# RPi_Extension_atx_power.net
KiCad netlist of a schematic drawn in EAGLE
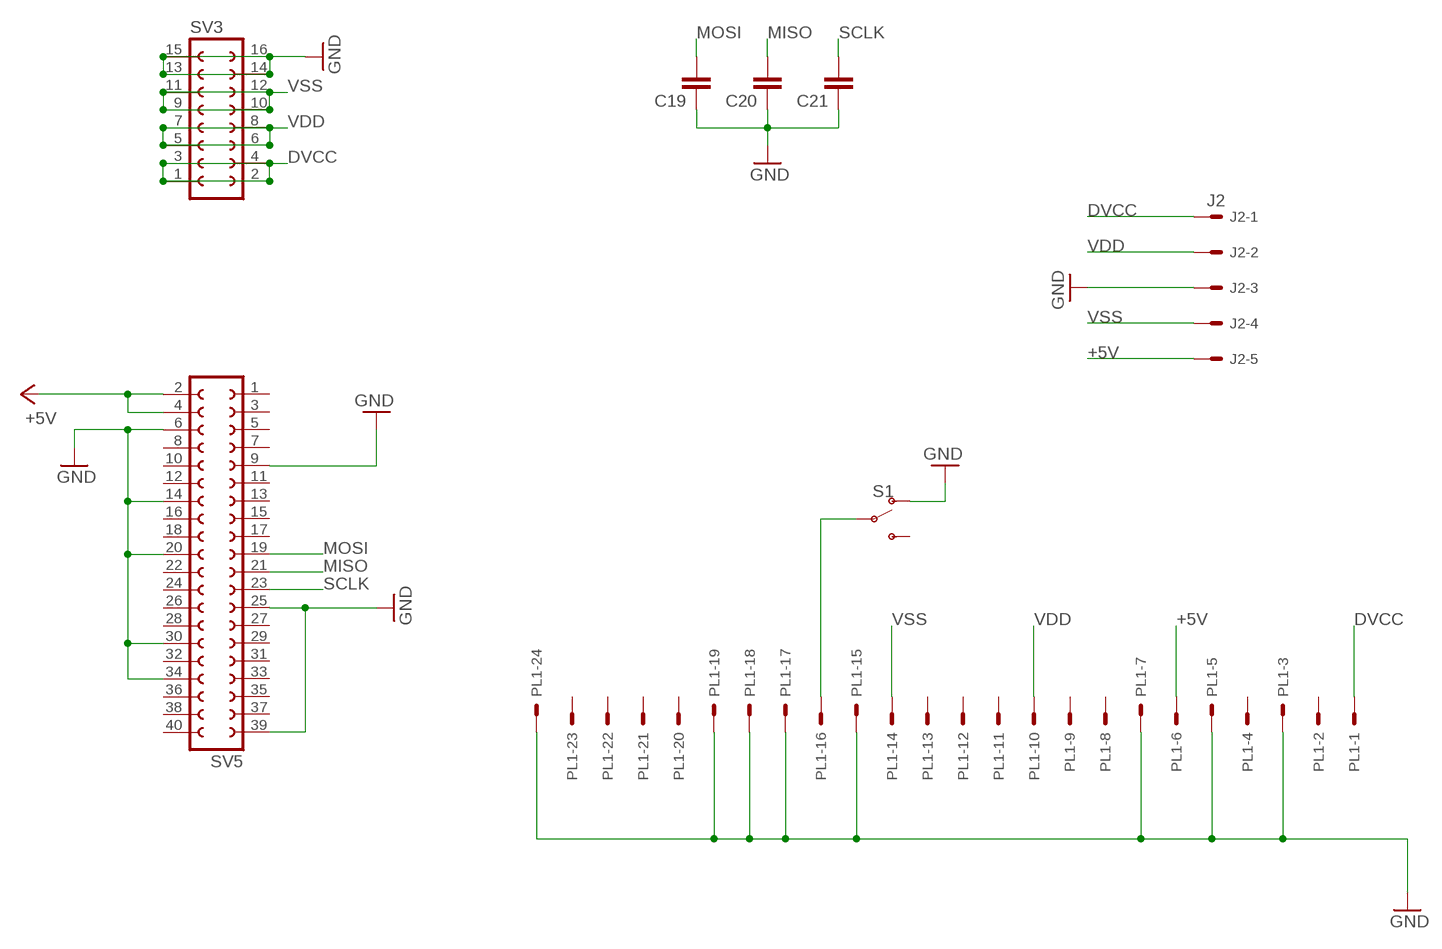
[diagram p0: schematic, sheet 1]

(export (version "E")
  (design (tool "Eeschema 10.0.6"))
  (components
    (comp (ref "C19")
      (value "C-EUC0603")
      (footprint "eagle-import:C0603")
      (libsource (lib "eagle-import") (part "C-EUC0603"))
    )
    (comp (ref "C20")
      (value "C-EUC0603")
      (footprint "eagle-import:C0603")
      (libsource (lib "eagle-import") (part "C-EUC0603"))
    )
    (comp (ref "C21")
      (value "C-EUC0603")
      (footprint "eagle-import:C0603")
      (libsource (lib "eagle-import") (part "C-EUC0603"))
    )
    (comp (ref "J2")
      (value "J2")
      (footprint "eagle-import:6410-05")
      (libsource (lib "eagle-import") (part "22-?-0527-2051"))
    )
    (comp (ref "PL1")
      (value "555X-24V")
      (footprint "eagle-import:5566-24")
      (libsource (lib "eagle-import") (part "555X-24V"))
    )
    (comp (ref "S1")
      (value "SWITCH-SPDT-PTH-11.6X4.0MM")
      (footprint "eagle-import:SWITCH_SPDT_PTH_11.6X4.0MM")
      (libsource (lib "eagle-import") (part "SWITCH-SPDT-PTH-11.6X4.0MM"))
    )
    (comp (ref "SV3")
      (value "FE08-2")
      (footprint "eagle-import:FE08-2")
      (libsource (lib "eagle-import") (part "FE08-2"))
    )
    (comp (ref "SV5")
      (value "FE20-2")
      (footprint "eagle-import:FE20-2")
      (libsource (lib "eagle-import") (part "FE20-2"))
    )
  )
  (nets
    (net (code "1") (name "+5V") (class "Default")
      (node (ref "J2") (pin "5") (pinfunction "S_5") (pintype "passive"))
      (node (ref "PL1") (pin "6") (pinfunction "S_6") (pintype "passive"))
      (node (ref "SV5") (pin "2") (pinfunction "2_2") (pintype "passive"))
      (node (ref "SV5") (pin "4") (pinfunction "4_4") (pintype "passive"))
    )
    (net (code "2") (name "/DVCC") (class "Default")
      (node (ref "J2") (pin "1") (pinfunction "S_1") (pintype "passive"))
      (node (ref "PL1") (pin "1") (pinfunction "S_1") (pintype "passive"))
      (node (ref "SV3") (pin "1") (pinfunction "1_1") (pintype "passive"))
      (node (ref "SV3") (pin "2") (pinfunction "2_2") (pintype "passive"))
      (node (ref "SV3") (pin "3") (pinfunction "3_3") (pintype "passive"))
      (node (ref "SV3") (pin "4") (pinfunction "4_4") (pintype "passive"))
    )
    (net (code "3") (name "/MISO") (class "Default")
      (node (ref "C20") (pin "2") (pinfunction "2_2") (pintype "passive"))
      (node (ref "SV5") (pin "21") (pinfunction "21_21") (pintype "passive"))
    )
    (net (code "4") (name "/MOSI") (class "Default")
      (node (ref "C19") (pin "2") (pinfunction "2_2") (pintype "passive"))
      (node (ref "SV5") (pin "19") (pinfunction "19_19") (pintype "passive"))
    )
    (net (code "5") (name "/SCLK") (class "Default")
      (node (ref "C21") (pin "2") (pinfunction "2_2") (pintype "passive"))
      (node (ref "SV5") (pin "23") (pinfunction "23_23") (pintype "passive"))
    )
    (net (code "6") (name "/VDD") (class "Default")
      (node (ref "J2") (pin "2") (pinfunction "S_2") (pintype "passive"))
      (node (ref "PL1") (pin "10") (pinfunction "S_10") (pintype "passive"))
      (node (ref "SV3") (pin "5") (pinfunction "5_5") (pintype "passive"))
      (node (ref "SV3") (pin "6") (pinfunction "6_6") (pintype "passive"))
      (node (ref "SV3") (pin "7") (pinfunction "7_7") (pintype "passive"))
      (node (ref "SV3") (pin "8") (pinfunction "8_8") (pintype "passive"))
    )
    (net (code "7") (name "/VSS") (class "Default")
      (node (ref "J2") (pin "4") (pinfunction "S_4") (pintype "passive"))
      (node (ref "PL1") (pin "14") (pinfunction "S_14") (pintype "passive"))
      (node (ref "SV3") (pin "10") (pinfunction "10_10") (pintype "passive"))
      (node (ref "SV3") (pin "11") (pinfunction "11_11") (pintype "passive"))
      (node (ref "SV3") (pin "12") (pinfunction "12_12") (pintype "passive"))
      (node (ref "SV3") (pin "9") (pinfunction "9_9") (pintype "passive"))
    )
    (net (code "8") (name "GND") (class "Default")
      (node (ref "C19") (pin "1") (pinfunction "1_1") (pintype "passive"))
      (node (ref "C20") (pin "1") (pinfunction "1_1") (pintype "passive"))
      (node (ref "C21") (pin "1") (pinfunction "1_1") (pintype "passive"))
      (node (ref "J2") (pin "3") (pinfunction "S_3") (pintype "passive"))
      (node (ref "PL1") (pin "15") (pinfunction "S_15") (pintype "passive"))
      (node (ref "PL1") (pin "17") (pinfunction "S_17") (pintype "passive"))
      (node (ref "PL1") (pin "18") (pinfunction "S_18") (pintype "passive"))
      (node (ref "PL1") (pin "19") (pinfunction "S_19") (pintype "passive"))
      (node (ref "PL1") (pin "24") (pinfunction "S_24") (pintype "passive"))
      (node (ref "PL1") (pin "3") (pinfunction "S_3") (pintype "passive"))
      (node (ref "PL1") (pin "5") (pinfunction "S_5") (pintype "passive"))
      (node (ref "PL1") (pin "7") (pinfunction "S_7") (pintype "passive"))
      (node (ref "S1") (pin "1") (pinfunction "O_1") (pintype "passive"))
      (node (ref "SV3") (pin "13") (pinfunction "13_13") (pintype "passive"))
      (node (ref "SV3") (pin "14") (pinfunction "14_14") (pintype "passive"))
      (node (ref "SV3") (pin "15") (pinfunction "15_15") (pintype "passive"))
      (node (ref "SV3") (pin "16") (pinfunction "16_16") (pintype "passive"))
      (node (ref "SV5") (pin "14") (pinfunction "14_14") (pintype "passive"))
      (node (ref "SV5") (pin "20") (pinfunction "20_20") (pintype "passive"))
      (node (ref "SV5") (pin "25") (pinfunction "25_25") (pintype "passive"))
      (node (ref "SV5") (pin "30") (pinfunction "30_30") (pintype "passive"))
      (node (ref "SV5") (pin "34") (pinfunction "34_34") (pintype "passive"))
      (node (ref "SV5") (pin "39") (pinfunction "39_39") (pintype "passive"))
      (node (ref "SV5") (pin "6") (pinfunction "6_6") (pintype "passive"))
      (node (ref "SV5") (pin "9") (pinfunction "9_9") (pintype "passive"))
    )
    (net (code "9") (name "Net-(PL1H-S)") (class "Default")
      (node (ref "PL1") (pin "16") (pinfunction "S_16") (pintype "passive"))
      (node (ref "S1") (pin "2") (pinfunction "P_2") (pintype "passive"))
    )
    (net (code "10") (name "unconnected-(PL1C-S-Pad11)") (class "Default")
      (node (ref "PL1") (pin "11") (pinfunction "S_11") (pintype "passive"))
    )
    (net (code "11") (name "unconnected-(PL1D-S-Pad12)") (class "Default")
      (node (ref "PL1") (pin "12") (pinfunction "S_12") (pintype "passive"))
    )
    (net (code "12") (name "unconnected-(PL1E-S-Pad13)") (class "Default")
      (node (ref "PL1") (pin "13") (pinfunction "S_13") (pintype "passive"))
    )
    (net (code "13") (name "unconnected-(PL1L-S-Pad2)") (class "Default")
      (node (ref "PL1") (pin "2") (pinfunction "S_2") (pintype "passive"))
    )
    (net (code "14") (name "unconnected-(PL1M-S-Pad20)") (class "Default")
      (node (ref "PL1") (pin "20") (pinfunction "S_20") (pintype "passive"))
    )
    (net (code "15") (name "unconnected-(PL1N-S-Pad21)") (class "Default")
      (node (ref "PL1") (pin "21") (pinfunction "S_21") (pintype "passive"))
    )
    (net (code "16") (name "unconnected-(PL1O-S-Pad22)") (class "Default")
      (node (ref "PL1") (pin "22") (pinfunction "S_22") (pintype "passive"))
    )
    (net (code "17") (name "unconnected-(PL1P-S-Pad23)") (class "Default")
      (node (ref "PL1") (pin "23") (pinfunction "S_23") (pintype "passive"))
    )
    (net (code "18") (name "unconnected-(PL1S-S-Pad4)") (class "Default")
      (node (ref "PL1") (pin "4") (pinfunction "S_4") (pintype "passive"))
    )
    (net (code "19") (name "unconnected-(PL1W-S-Pad8)") (class "Default")
      (node (ref "PL1") (pin "8") (pinfunction "S_8") (pintype "passive"))
    )
    (net (code "20") (name "unconnected-(PL1X-S-Pad9)") (class "Default")
      (node (ref "PL1") (pin "9") (pinfunction "S_9") (pintype "passive"))
    )
    (net (code "21") (name "unconnected-(S1-S-Pad3)") (class "Default")
      (node (ref "S1") (pin "3") (pinfunction "S_3") (pintype "passive"))
    )
    (net (code "22") (name "unconnected-(SV5-Pad1)") (class "Default")
      (node (ref "SV5") (pin "1") (pinfunction "1_1") (pintype "passive"))
    )
    (net (code "23") (name "unconnected-(SV5-Pad3)") (class "Default")
      (node (ref "SV5") (pin "3") (pinfunction "3_3") (pintype "passive"))
    )
    (net (code "24") (name "unconnected-(SV5-Pad5)") (class "Default")
      (node (ref "SV5") (pin "5") (pinfunction "5_5") (pintype "passive"))
    )
    (net (code "25") (name "unconnected-(SV5-Pad7)") (class "Default")
      (node (ref "SV5") (pin "7") (pinfunction "7_7") (pintype "passive"))
    )
    (net (code "26") (name "unconnected-(SV5-Pad8)") (class "Default")
      (node (ref "SV5") (pin "8") (pinfunction "8_8") (pintype "passive"))
    )
    (net (code "27") (name "unconnected-(SV5-Pad10)") (class "Default")
      (node (ref "SV5") (pin "10") (pinfunction "10_10") (pintype "passive"))
    )
    (net (code "28") (name "unconnected-(SV5-Pad11)") (class "Default")
      (node (ref "SV5") (pin "11") (pinfunction "11_11") (pintype "passive"))
    )
    (net (code "29") (name "unconnected-(SV5-Pad12)") (class "Default")
      (node (ref "SV5") (pin "12") (pinfunction "12_12") (pintype "passive"))
    )
    (net (code "30") (name "unconnected-(SV5-Pad13)") (class "Default")
      (node (ref "SV5") (pin "13") (pinfunction "13_13") (pintype "passive"))
    )
    (net (code "31") (name "unconnected-(SV5-Pad15)") (class "Default")
      (node (ref "SV5") (pin "15") (pinfunction "15_15") (pintype "passive"))
    )
    (net (code "32") (name "unconnected-(SV5-Pad16)") (class "Default")
      (node (ref "SV5") (pin "16") (pinfunction "16_16") (pintype "passive"))
    )
    (net (code "33") (name "unconnected-(SV5-Pad17)") (class "Default")
      (node (ref "SV5") (pin "17") (pinfunction "17_17") (pintype "passive"))
    )
    (net (code "34") (name "unconnected-(SV5-Pad18)") (class "Default")
      (node (ref "SV5") (pin "18") (pinfunction "18_18") (pintype "passive"))
    )
    (net (code "35") (name "unconnected-(SV5-Pad22)") (class "Default")
      (node (ref "SV5") (pin "22") (pinfunction "22_22") (pintype "passive"))
    )
    (net (code "36") (name "unconnected-(SV5-Pad24)") (class "Default")
      (node (ref "SV5") (pin "24") (pinfunction "24_24") (pintype "passive"))
    )
    (net (code "37") (name "unconnected-(SV5-Pad26)") (class "Default")
      (node (ref "SV5") (pin "26") (pinfunction "26_26") (pintype "passive"))
    )
    (net (code "38") (name "unconnected-(SV5-Pad27)") (class "Default")
      (node (ref "SV5") (pin "27") (pinfunction "27_27") (pintype "passive"))
    )
    (net (code "39") (name "unconnected-(SV5-Pad28)") (class "Default")
      (node (ref "SV5") (pin "28") (pinfunction "28_28") (pintype "passive"))
    )
    (net (code "40") (name "unconnected-(SV5-Pad29)") (class "Default")
      (node (ref "SV5") (pin "29") (pinfunction "29_29") (pintype "passive"))
    )
    (net (code "41") (name "unconnected-(SV5-Pad31)") (class "Default")
      (node (ref "SV5") (pin "31") (pinfunction "31_31") (pintype "passive"))
    )
    (net (code "42") (name "unconnected-(SV5-Pad32)") (class "Default")
      (node (ref "SV5") (pin "32") (pinfunction "32_32") (pintype "passive"))
    )
    (net (code "43") (name "unconnected-(SV5-Pad33)") (class "Default")
      (node (ref "SV5") (pin "33") (pinfunction "33_33") (pintype "passive"))
    )
    (net (code "44") (name "unconnected-(SV5-Pad35)") (class "Default")
      (node (ref "SV5") (pin "35") (pinfunction "35_35") (pintype "passive"))
    )
    (net (code "45") (name "unconnected-(SV5-Pad36)") (class "Default")
      (node (ref "SV5") (pin "36") (pinfunction "36_36") (pintype "passive"))
    )
    (net (code "46") (name "unconnected-(SV5-Pad37)") (class "Default")
      (node (ref "SV5") (pin "37") (pinfunction "37_37") (pintype "passive"))
    )
    (net (code "47") (name "unconnected-(SV5-Pad38)") (class "Default")
      (node (ref "SV5") (pin "38") (pinfunction "38_38") (pintype "passive"))
    )
    (net (code "48") (name "unconnected-(SV5-Pad40)") (class "Default")
      (node (ref "SV5") (pin "40") (pinfunction "40_40") (pintype "passive"))
    )
  )
)
